# Clock.net
KiCad netlist of a schematic drawn in Altium Designer
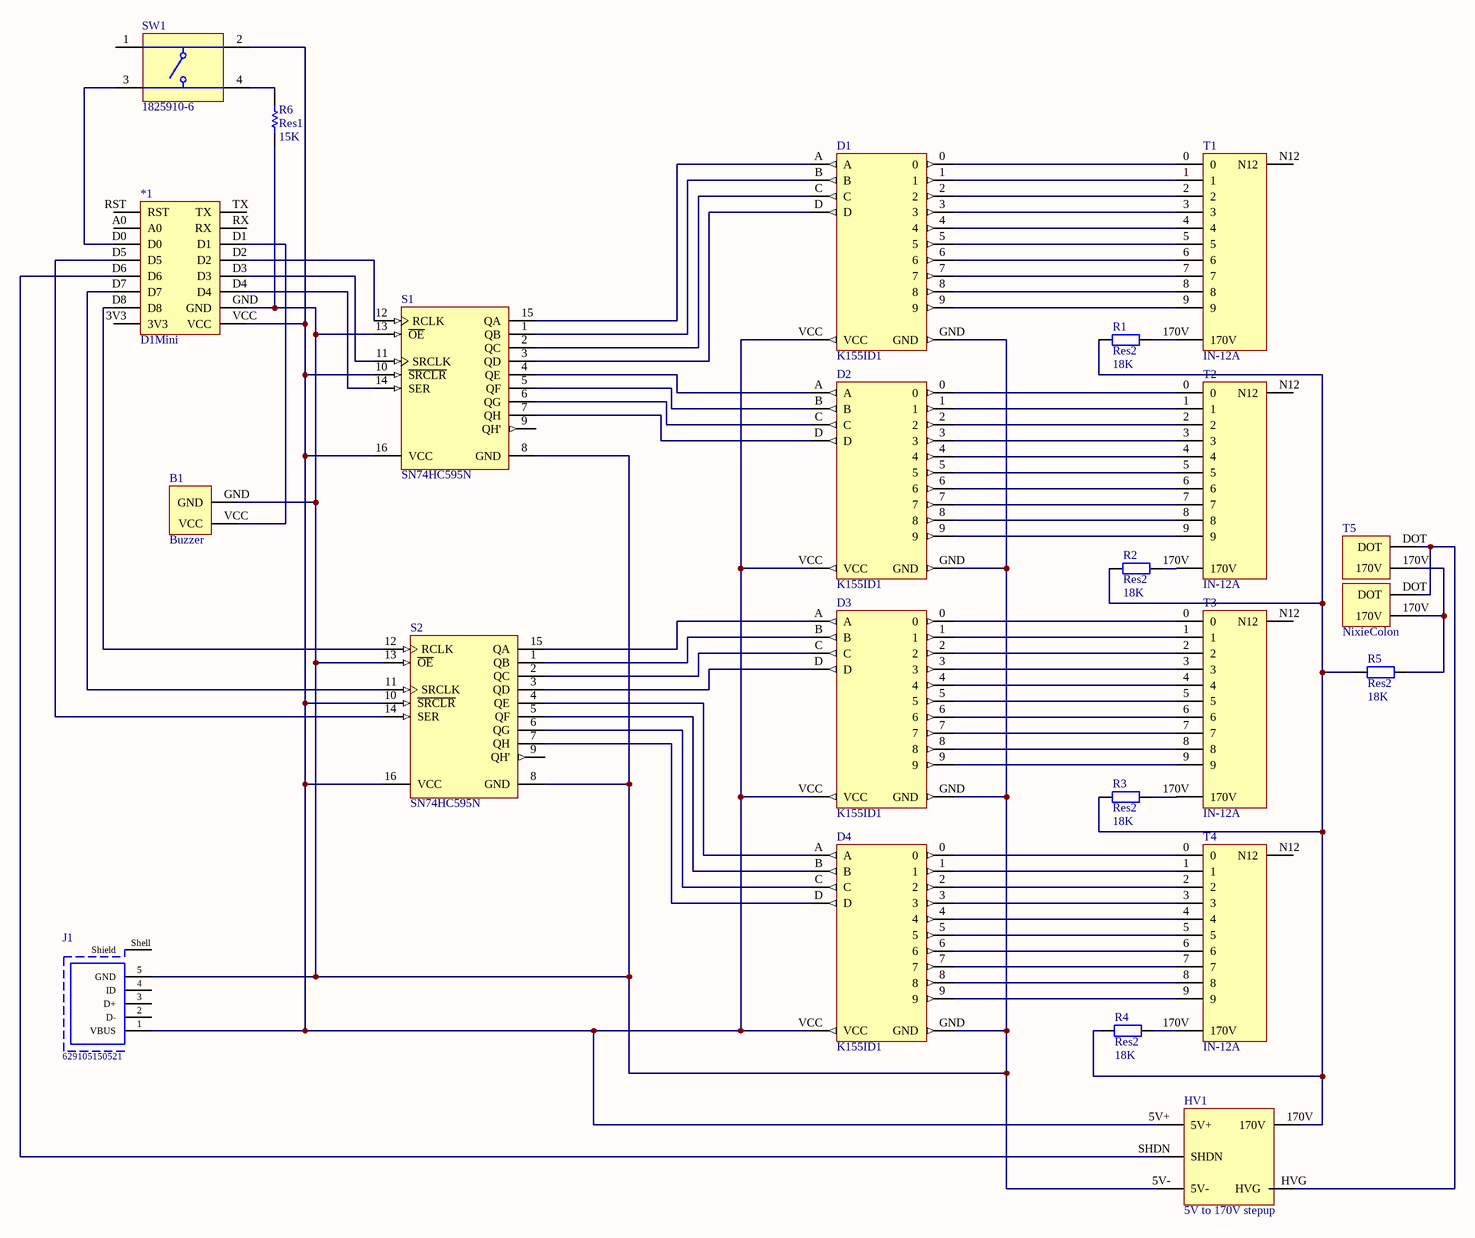
[diagram p0: Clock.SchDoc]

(export (version "E")
  (design (tool "Eeschema 10.0.6"))
  (components
    (comp (ref "*1")
      (value "D1Mini")
      (footprint "DIP16-WemosD1Mini")
      (libsource (lib "NixieTubeClock") (part "D1Mini"))
    )
    (comp (ref "B1") (value "Buzzer") (footprint "Buzzer") (libsource (lib "NixieTubeClock") (part "Buzzer")))
    (comp (ref "D1")
      (value "K155ID1")
      (footprint "DIP16")
      (libsource (lib "NixieTubeClock") (part "K155ID1"))
    )
    (comp (ref "D2")
      (value "K155ID1")
      (footprint "DIP16")
      (libsource (lib "NixieTubeClock") (part "K155ID1"))
    )
    (comp (ref "D3")
      (value "K155ID1")
      (footprint "DIP16")
      (libsource (lib "NixieTubeClock") (part "K155ID1"))
    )
    (comp (ref "D4")
      (value "K155ID1")
      (footprint "DIP16")
      (libsource (lib "NixieTubeClock") (part "K155ID1"))
    )
    (comp (ref "HV1")
      (value "5V to 170V stepup")
      (footprint "5V to 170V stepup")
      (libsource (lib "NixieTubeClock") (part "5V to 170V stepup"))
    )
    (comp (ref "J1")
      (value "629105150521")
      (footprint "629105150521")
      (description "Micro USB 2.0 Type B Receptacle WR-COM, Horizontal, SMT, with Pegs, High Current at Pin 1 & Pin 5")
      (fields (field (name "MANUFACTURER") "Wurth Elektronik") (field (name "PUBLISHER") "WurthElektronik"))
      (libsource (lib "Altium Content Vault") (part "WE-USB-5-1SHLD"))
    )
    (comp (ref "R1")
      (value "Res2")
      (footprint "AXIAL-0.6")
      (description "Resistor")
      (fields (field (name "ALTIUM_VALUE") "18K") (field (name "PUBLISHER") "Altium Limited"))
      (libsource (lib "Miscellaneous Devices") (part "Res2"))
    )
    (comp (ref "R2")
      (value "Res2")
      (footprint "AXIAL-0.6")
      (description "Resistor")
      (fields (field (name "ALTIUM_VALUE") "18K") (field (name "PUBLISHER") "Altium Limited"))
      (libsource (lib "Miscellaneous Devices") (part "Res2"))
    )
    (comp (ref "R3")
      (value "Res2")
      (footprint "AXIAL-0.6")
      (description "Resistor")
      (fields (field (name "ALTIUM_VALUE") "18K") (field (name "PUBLISHER") "Altium Limited"))
      (libsource (lib "Miscellaneous Devices") (part "Res2"))
    )
    (comp (ref "R4")
      (value "Res2")
      (footprint "AXIAL-0.6")
      (description "Resistor")
      (fields (field (name "ALTIUM_VALUE") "18K") (field (name "PUBLISHER") "Altium Limited"))
      (libsource (lib "Miscellaneous Devices") (part "Res2"))
    )
    (comp (ref "R5")
      (value "Res2")
      (footprint "AXIAL-0.6")
      (description "Resistor")
      (fields (field (name "ALTIUM_VALUE") "18K") (field (name "PUBLISHER") "Altium Limited"))
      (libsource (lib "Miscellaneous Devices") (part "Res2"))
    )
    (comp (ref "R6")
      (value "Res1")
      (footprint "AXIAL-0.3")
      (description "Resistor")
      (fields (field (name "ALTIUM_VALUE") "15K") (field (name "PUBLISHER") "Altium Limited"))
      (libsource (lib "Miscellaneous Devices") (part "Res1"))
    )
    (comp (ref "S1")
      (value "SN74HC595N")
      (footprint "N0016A")
      (description "8-Bit Shift Registers With 3-State Output Registers, N0016A, TUBE")
      (fields
        (field (name "GENERIC PART NUMBER") "SN74HC595")
        (field (name "MANUFACTURER") "Texas Instruments")
      )
      (libsource (lib "Altium Content Vault") (part "TI-SN74XHCT595X_SN74LV595A-16"))
    )
    (comp (ref "S2")
      (value "SN74HC595N")
      (footprint "N0016A")
      (description "8-Bit Shift Registers With 3-State Output Registers, N0016A, TUBE")
      (fields
        (field (name "GENERIC PART NUMBER") "SN74HC595")
        (field (name "MANUFACTURER") "Texas Instruments")
      )
      (libsource (lib "Altium Content Vault") (part "TI-SN74XHCT595X_SN74LV595A-16"))
    )
    (comp (ref "SW1")
      (value "1825910-6")
      (footprint "TECO-1825910-6_V")
      (description "Tact Switch, SPST-NO, 0.05 A, -35 to 85 degC, 4-Pin THD, RoHS, Bulk")
      (fields (field (name "MANUFACTURER") "TE Connectivity"))
      (libsource (lib "Altium Content Vault") (part "SW-SPST-4_A"))
    )
    (comp (ref "T1") (value "IN-12A") (footprint "IN-12A") (libsource (lib "NixieTubeClock") (part "IN-12A")))
    (comp (ref "T2") (value "IN-12A") (footprint "IN-12A") (libsource (lib "NixieTubeClock") (part "IN-12A")))
    (comp (ref "T3") (value "IN-12A") (footprint "IN-12A") (libsource (lib "NixieTubeClock") (part "IN-12A")))
    (comp (ref "T4") (value "IN-12A") (footprint "IN-12A") (libsource (lib "NixieTubeClock") (part "IN-12A")))
    (comp (ref "T5")
      (value "NixieColon")
      (footprint "COLON IN-12A")
      (libsource (lib "NixieTubeClock") (part "NixieColon"))
    )
  )
  (nets
    (net (code "1") (name "Net-(*1-PadD0)") (class "Default")
      (node (ref "*1") (pin "D0") (pinfunction "D0_D0") (pintype "passive"))
      (node (ref "SW1") (pin "3") (pinfunction "3_3") (pintype "passive"))
    )
    (net (code "2") (name "Net-(*1-PadD1)") (class "Default")
      (node (ref "*1") (pin "D1") (pinfunction "D1_D1") (pintype "passive"))
      (node (ref "B1") (pin "VCC") (pinfunction "VCC_VCC") (pintype "passive"))
    )
    (net (code "3") (name "Net-(*1-PadD6)") (class "Default")
      (node (ref "*1") (pin "D6") (pinfunction "D6_D6") (pintype "passive"))
      (node (ref "HV1") (pin "SHDN") (pinfunction "SHDN_SHDN") (pintype "passive"))
    )
    (net (code "4") (name "Net-(D1-Pad0)") (class "Default")
      (node (ref "D1") (pin "0") (pinfunction "0_0") (pintype "output"))
      (node (ref "T1") (pin "0") (pinfunction "0_0") (pintype "passive"))
    )
    (net (code "5") (name "Net-(D1-Pad1)") (class "Default")
      (node (ref "D1") (pin "1") (pinfunction "1_1") (pintype "output"))
      (node (ref "T1") (pin "1") (pinfunction "1_1") (pintype "passive"))
    )
    (net (code "6") (name "Net-(D1-Pad2)") (class "Default")
      (node (ref "D1") (pin "2") (pinfunction "2_2") (pintype "output"))
      (node (ref "T1") (pin "2") (pinfunction "2_2") (pintype "passive"))
    )
    (net (code "7") (name "Net-(D1-Pad3)") (class "Default")
      (node (ref "D1") (pin "3") (pinfunction "3_3") (pintype "output"))
      (node (ref "T1") (pin "3") (pinfunction "3_3") (pintype "passive"))
    )
    (net (code "8") (name "Net-(D1-Pad4)") (class "Default")
      (node (ref "D1") (pin "4") (pinfunction "4_4") (pintype "output"))
      (node (ref "T1") (pin "4") (pinfunction "4_4") (pintype "passive"))
    )
    (net (code "9") (name "Net-(D1-Pad5)") (class "Default")
      (node (ref "D1") (pin "5") (pinfunction "5_5") (pintype "output"))
      (node (ref "T1") (pin "5") (pinfunction "5_5") (pintype "passive"))
    )
    (net (code "10") (name "Net-(D1-Pad6)") (class "Default")
      (node (ref "D1") (pin "6") (pinfunction "6_6") (pintype "output"))
      (node (ref "T1") (pin "6") (pinfunction "6_6") (pintype "passive"))
    )
    (net (code "11") (name "Net-(D1-Pad7)") (class "Default")
      (node (ref "D1") (pin "7") (pinfunction "7_7") (pintype "output"))
      (node (ref "T1") (pin "7") (pinfunction "7_7") (pintype "passive"))
    )
    (net (code "12") (name "Net-(D1-Pad8)") (class "Default")
      (node (ref "D1") (pin "8") (pinfunction "8_8") (pintype "output"))
      (node (ref "T1") (pin "8") (pinfunction "8_8") (pintype "passive"))
    )
    (net (code "13") (name "Net-(D1-Pad9)") (class "Default")
      (node (ref "D1") (pin "9") (pinfunction "9_9") (pintype "output"))
      (node (ref "T1") (pin "9") (pinfunction "9_9") (pintype "passive"))
    )
    (net (code "14") (name "Net-(D2-Pad0)") (class "Default")
      (node (ref "D2") (pin "0") (pinfunction "0_0") (pintype "output"))
      (node (ref "T2") (pin "0") (pinfunction "0_0") (pintype "passive"))
    )
    (net (code "15") (name "Net-(D2-Pad1)") (class "Default")
      (node (ref "D2") (pin "1") (pinfunction "1_1") (pintype "output"))
      (node (ref "T2") (pin "1") (pinfunction "1_1") (pintype "passive"))
    )
    (net (code "16") (name "Net-(D2-Pad2)") (class "Default")
      (node (ref "D2") (pin "2") (pinfunction "2_2") (pintype "output"))
      (node (ref "T2") (pin "2") (pinfunction "2_2") (pintype "passive"))
    )
    (net (code "17") (name "Net-(D2-Pad3)") (class "Default")
      (node (ref "D2") (pin "3") (pinfunction "3_3") (pintype "output"))
      (node (ref "T2") (pin "3") (pinfunction "3_3") (pintype "passive"))
    )
    (net (code "18") (name "Net-(D2-Pad4)") (class "Default")
      (node (ref "D2") (pin "4") (pinfunction "4_4") (pintype "output"))
      (node (ref "T2") (pin "4") (pinfunction "4_4") (pintype "passive"))
    )
    (net (code "19") (name "Net-(D2-Pad5)") (class "Default")
      (node (ref "D2") (pin "5") (pinfunction "5_5") (pintype "output"))
      (node (ref "T2") (pin "5") (pinfunction "5_5") (pintype "passive"))
    )
    (net (code "20") (name "Net-(D2-Pad6)") (class "Default")
      (node (ref "D2") (pin "6") (pinfunction "6_6") (pintype "output"))
      (node (ref "T2") (pin "6") (pinfunction "6_6") (pintype "passive"))
    )
    (net (code "21") (name "Net-(D2-Pad7)") (class "Default")
      (node (ref "D2") (pin "7") (pinfunction "7_7") (pintype "output"))
      (node (ref "T2") (pin "7") (pinfunction "7_7") (pintype "passive"))
    )
    (net (code "22") (name "Net-(D2-Pad8)") (class "Default")
      (node (ref "D2") (pin "8") (pinfunction "8_8") (pintype "output"))
      (node (ref "T2") (pin "8") (pinfunction "8_8") (pintype "passive"))
    )
    (net (code "23") (name "Net-(D2-Pad9)") (class "Default")
      (node (ref "D2") (pin "9") (pinfunction "9_9") (pintype "output"))
      (node (ref "T2") (pin "9") (pinfunction "9_9") (pintype "passive"))
    )
    (net (code "24") (name "Net-(D3-Pad0)") (class "Default")
      (node (ref "D3") (pin "0") (pinfunction "0_0") (pintype "output"))
      (node (ref "T3") (pin "0") (pinfunction "0_0") (pintype "passive"))
    )
    (net (code "25") (name "Net-(D3-Pad1)") (class "Default")
      (node (ref "D3") (pin "1") (pinfunction "1_1") (pintype "output"))
      (node (ref "T3") (pin "1") (pinfunction "1_1") (pintype "passive"))
    )
    (net (code "26") (name "Net-(D3-Pad2)") (class "Default")
      (node (ref "D3") (pin "2") (pinfunction "2_2") (pintype "output"))
      (node (ref "T3") (pin "2") (pinfunction "2_2") (pintype "passive"))
    )
    (net (code "27") (name "Net-(D3-Pad3)") (class "Default")
      (node (ref "D3") (pin "3") (pinfunction "3_3") (pintype "output"))
      (node (ref "T3") (pin "3") (pinfunction "3_3") (pintype "passive"))
    )
    (net (code "28") (name "Net-(D3-Pad4)") (class "Default")
      (node (ref "D3") (pin "4") (pinfunction "4_4") (pintype "output"))
      (node (ref "T3") (pin "4") (pinfunction "4_4") (pintype "passive"))
    )
    (net (code "29") (name "Net-(D3-Pad5)") (class "Default")
      (node (ref "D3") (pin "5") (pinfunction "5_5") (pintype "output"))
      (node (ref "T3") (pin "5") (pinfunction "5_5") (pintype "passive"))
    )
    (net (code "30") (name "Net-(D3-Pad6)") (class "Default")
      (node (ref "D3") (pin "6") (pinfunction "6_6") (pintype "output"))
      (node (ref "T3") (pin "6") (pinfunction "6_6") (pintype "passive"))
    )
    (net (code "31") (name "Net-(D3-Pad7)") (class "Default")
      (node (ref "D3") (pin "7") (pinfunction "7_7") (pintype "output"))
      (node (ref "T3") (pin "7") (pinfunction "7_7") (pintype "passive"))
    )
    (net (code "32") (name "Net-(D3-Pad8)") (class "Default")
      (node (ref "D3") (pin "8") (pinfunction "8_8") (pintype "output"))
      (node (ref "T3") (pin "8") (pinfunction "8_8") (pintype "passive"))
    )
    (net (code "33") (name "Net-(D3-Pad9)") (class "Default")
      (node (ref "D3") (pin "9") (pinfunction "9_9") (pintype "output"))
      (node (ref "T3") (pin "9") (pinfunction "9_9") (pintype "passive"))
    )
    (net (code "34") (name "Net-(D4-Pad0)") (class "Default")
      (node (ref "D4") (pin "0") (pinfunction "0_0") (pintype "output"))
      (node (ref "T4") (pin "0") (pinfunction "0_0") (pintype "passive"))
    )
    (net (code "35") (name "Net-(D4-Pad1)") (class "Default")
      (node (ref "D4") (pin "1") (pinfunction "1_1") (pintype "output"))
      (node (ref "T4") (pin "1") (pinfunction "1_1") (pintype "passive"))
    )
    (net (code "36") (name "Net-(D4-Pad2)") (class "Default")
      (node (ref "D4") (pin "2") (pinfunction "2_2") (pintype "output"))
      (node (ref "T4") (pin "2") (pinfunction "2_2") (pintype "passive"))
    )
    (net (code "37") (name "Net-(D4-Pad3)") (class "Default")
      (node (ref "D4") (pin "3") (pinfunction "3_3") (pintype "output"))
      (node (ref "T4") (pin "3") (pinfunction "3_3") (pintype "passive"))
    )
    (net (code "38") (name "Net-(D4-Pad4)") (class "Default")
      (node (ref "D4") (pin "4") (pinfunction "4_4") (pintype "output"))
      (node (ref "T4") (pin "4") (pinfunction "4_4") (pintype "passive"))
    )
    (net (code "39") (name "Net-(D4-Pad5)") (class "Default")
      (node (ref "D4") (pin "5") (pinfunction "5_5") (pintype "output"))
      (node (ref "T4") (pin "5") (pinfunction "5_5") (pintype "passive"))
    )
    (net (code "40") (name "Net-(D4-Pad6)") (class "Default")
      (node (ref "D4") (pin "6") (pinfunction "6_6") (pintype "output"))
      (node (ref "T4") (pin "6") (pinfunction "6_6") (pintype "passive"))
    )
    (net (code "41") (name "Net-(D4-Pad7)") (class "Default")
      (node (ref "D4") (pin "7") (pinfunction "7_7") (pintype "output"))
      (node (ref "T4") (pin "7") (pinfunction "7_7") (pintype "passive"))
    )
    (net (code "42") (name "Net-(D4-Pad8)") (class "Default")
      (node (ref "D4") (pin "8") (pinfunction "8_8") (pintype "output"))
      (node (ref "T4") (pin "8") (pinfunction "8_8") (pintype "passive"))
    )
    (net (code "43") (name "Net-(D4-Pad9)") (class "Default")
      (node (ref "D4") (pin "9") (pinfunction "9_9") (pintype "output"))
      (node (ref "T4") (pin "9") (pinfunction "9_9") (pintype "passive"))
    )
    (net (code "44") (name "Net-(HV1-Pad170V)") (class "Default")
      (node (ref "HV1") (pin "170V") (pinfunction "170V_170V") (pintype "passive"))
      (node (ref "R1") (pin "2") (pinfunction "2_2") (pintype "passive"))
      (node (ref "R2") (pin "2") (pinfunction "2_2") (pintype "passive"))
      (node (ref "R3") (pin "2") (pinfunction "2_2") (pintype "passive"))
      (node (ref "R4") (pin "2") (pinfunction "2_2") (pintype "passive"))
      (node (ref "R5") (pin "2") (pinfunction "2_2") (pintype "passive"))
    )
    (net (code "45") (name "Net-(HV1-PadHVG)") (class "Default")
      (node (ref "HV1") (pin "HVG") (pinfunction "HVG_HVG") (pintype "passive"))
      (node (ref "T5") (pin "DOT") (pinfunction "DOT_DOT") (pintype "passive"))
    )
    (net (code "46") (name "Net-(J1-GND)") (class "Default")
      (node (ref "*1") (pin "GND") (pinfunction "GND_GND") (pintype "passive"))
      (node (ref "B1") (pin "GND") (pinfunction "GND_GND") (pintype "passive"))
      (node (ref "D1") (pin "GND") (pinfunction "GND_GND") (pintype "output"))
      (node (ref "D2") (pin "GND") (pinfunction "GND_GND") (pintype "output"))
      (node (ref "D3") (pin "GND") (pinfunction "GND_GND") (pintype "output"))
      (node (ref "D4") (pin "GND") (pinfunction "GND_GND") (pintype "output"))
      (node (ref "HV1") (pin "5V-") (pinfunction "5V-_5V-") (pintype "passive"))
      (node (ref "J1") (pin "5") (pinfunction "GND_5") (pintype "passive"))
      (node (ref "R6") (pin "1") (pinfunction "1_1") (pintype "passive"))
      (node (ref "S1") (pin "13") (pinfunction "~{OE}_13") (pintype "input"))
      (node (ref "S1") (pin "8") (pinfunction "GND_8") (pintype "power_in"))
      (node (ref "S2") (pin "13") (pinfunction "~{OE}_13") (pintype "input"))
      (node (ref "S2") (pin "8") (pinfunction "GND_8") (pintype "power_in"))
    )
    (net (code "47") (name "Net-(J1-VBUS)") (class "Default")
      (node (ref "*1") (pin "VCC") (pinfunction "VCC_VCC") (pintype "passive"))
      (node (ref "D1") (pin "VCC") (pinfunction "VCC_VCC") (pintype "output"))
      (node (ref "D2") (pin "VCC") (pinfunction "VCC_VCC") (pintype "output"))
      (node (ref "D3") (pin "VCC") (pinfunction "VCC_VCC") (pintype "output"))
      (node (ref "D4") (pin "VCC") (pinfunction "VCC_VCC") (pintype "output"))
      (node (ref "HV1") (pin "5V+") (pinfunction "5V+_5V+") (pintype "passive"))
      (node (ref "J1") (pin "1") (pinfunction "VBUS_1") (pintype "passive"))
      (node (ref "S1") (pin "10") (pinfunction "~{SRCLR}_10") (pintype "input"))
      (node (ref "S1") (pin "16") (pinfunction "VCC_16") (pintype "power_in"))
      (node (ref "S2") (pin "10") (pinfunction "~{SRCLR}_10") (pintype "input"))
      (node (ref "S2") (pin "16") (pinfunction "VCC_16") (pintype "power_in"))
      (node (ref "SW1") (pin "2") (pinfunction "2_2") (pintype "passive"))
    )
    (net (code "48") (name "Net-(R1-Pad1)") (class "Default")
      (node (ref "R1") (pin "1") (pinfunction "1_1") (pintype "passive"))
      (node (ref "T1") (pin "170V") (pinfunction "170V_170V") (pintype "passive"))
    )
    (net (code "49") (name "Net-(R2-Pad1)") (class "Default")
      (node (ref "R2") (pin "1") (pinfunction "1_1") (pintype "passive"))
      (node (ref "T2") (pin "170V") (pinfunction "170V_170V") (pintype "passive"))
    )
    (net (code "50") (name "Net-(R3-Pad1)") (class "Default")
      (node (ref "R3") (pin "1") (pinfunction "1_1") (pintype "passive"))
      (node (ref "T3") (pin "170V") (pinfunction "170V_170V") (pintype "passive"))
    )
    (net (code "51") (name "Net-(R4-Pad1)") (class "Default")
      (node (ref "R4") (pin "1") (pinfunction "1_1") (pintype "passive"))
      (node (ref "T4") (pin "170V") (pinfunction "170V_170V") (pintype "passive"))
    )
    (net (code "52") (name "Net-(R5-Pad1)") (class "Default")
      (node (ref "R5") (pin "1") (pinfunction "1_1") (pintype "passive"))
      (node (ref "T5") (pin "170V") (pinfunction "170V_170V") (pintype "passive"))
    )
    (net (code "53") (name "Net-(R6-Pad2)") (class "Default")
      (node (ref "R6") (pin "2") (pinfunction "2_2") (pintype "passive"))
      (node (ref "SW1") (pin "4") (pinfunction "4_4") (pintype "passive"))
    )
    (net (code "54") (name "Net-(S1-QA)") (class "Default")
      (node (ref "D1") (pin "A") (pinfunction "A_A") (pintype "output"))
      (node (ref "S1") (pin "15") (pinfunction "QA_15") (pintype "tri_state"))
    )
    (net (code "55") (name "Net-(S1-QB)") (class "Default")
      (node (ref "D1") (pin "B") (pinfunction "B_B") (pintype "output"))
      (node (ref "S1") (pin "1") (pinfunction "QB_1") (pintype "tri_state"))
    )
    (net (code "56") (name "Net-(S1-QC)") (class "Default")
      (node (ref "D1") (pin "C") (pinfunction "C_C") (pintype "output"))
      (node (ref "S1") (pin "2") (pinfunction "QC_2") (pintype "tri_state"))
    )
    (net (code "57") (name "Net-(S1-QD)") (class "Default")
      (node (ref "D1") (pin "D") (pinfunction "D_D") (pintype "output"))
      (node (ref "S1") (pin "3") (pinfunction "QD_3") (pintype "tri_state"))
    )
    (net (code "58") (name "Net-(S1-QE)") (class "Default")
      (node (ref "D2") (pin "A") (pinfunction "A_A") (pintype "output"))
      (node (ref "S1") (pin "4") (pinfunction "QE_4") (pintype "tri_state"))
    )
    (net (code "59") (name "Net-(S1-QF)") (class "Default")
      (node (ref "D2") (pin "B") (pinfunction "B_B") (pintype "output"))
      (node (ref "S1") (pin "5") (pinfunction "QF_5") (pintype "tri_state"))
    )
    (net (code "60") (name "Net-(S1-QG)") (class "Default")
      (node (ref "D2") (pin "C") (pinfunction "C_C") (pintype "output"))
      (node (ref "S1") (pin "6") (pinfunction "QG_6") (pintype "tri_state"))
    )
    (net (code "61") (name "Net-(S1-QH)") (class "Default")
      (node (ref "D2") (pin "D") (pinfunction "D_D") (pintype "output"))
      (node (ref "S1") (pin "7") (pinfunction "QH_7") (pintype "tri_state"))
    )
    (net (code "62") (name "Net-(S1-RCLK)") (class "Default")
      (node (ref "*1") (pin "D2") (pinfunction "D2_D2") (pintype "passive"))
      (node (ref "S1") (pin "12") (pinfunction "RCLK_12") (pintype "input"))
    )
    (net (code "63") (name "Net-(S1-SER)") (class "Default")
      (node (ref "*1") (pin "D4") (pinfunction "D4_D4") (pintype "passive"))
      (node (ref "S1") (pin "14") (pinfunction "SER_14") (pintype "input"))
    )
    (net (code "64") (name "Net-(S1-SRCLK)") (class "Default")
      (node (ref "*1") (pin "D3") (pinfunction "D3_D3") (pintype "passive"))
      (node (ref "S1") (pin "11") (pinfunction "SRCLK_11") (pintype "input"))
    )
    (net (code "65") (name "Net-(S2-QA)") (class "Default")
      (node (ref "D3") (pin "A") (pinfunction "A_A") (pintype "output"))
      (node (ref "S2") (pin "15") (pinfunction "QA_15") (pintype "tri_state"))
    )
    (net (code "66") (name "Net-(S2-QB)") (class "Default")
      (node (ref "D3") (pin "B") (pinfunction "B_B") (pintype "output"))
      (node (ref "S2") (pin "1") (pinfunction "QB_1") (pintype "tri_state"))
    )
    (net (code "67") (name "Net-(S2-QC)") (class "Default")
      (node (ref "D3") (pin "C") (pinfunction "C_C") (pintype "output"))
      (node (ref "S2") (pin "2") (pinfunction "QC_2") (pintype "tri_state"))
    )
    (net (code "68") (name "Net-(S2-QD)") (class "Default")
      (node (ref "D3") (pin "D") (pinfunction "D_D") (pintype "output"))
      (node (ref "S2") (pin "3") (pinfunction "QD_3") (pintype "tri_state"))
    )
    (net (code "69") (name "Net-(S2-QE)") (class "Default")
      (node (ref "D4") (pin "A") (pinfunction "A_A") (pintype "output"))
      (node (ref "S2") (pin "4") (pinfunction "QE_4") (pintype "tri_state"))
    )
    (net (code "70") (name "Net-(S2-QF)") (class "Default")
      (node (ref "D4") (pin "B") (pinfunction "B_B") (pintype "output"))
      (node (ref "S2") (pin "5") (pinfunction "QF_5") (pintype "tri_state"))
    )
    (net (code "71") (name "Net-(S2-QG)") (class "Default")
      (node (ref "D4") (pin "C") (pinfunction "C_C") (pintype "output"))
      (node (ref "S2") (pin "6") (pinfunction "QG_6") (pintype "tri_state"))
    )
    (net (code "72") (name "Net-(S2-QH)") (class "Default")
      (node (ref "D4") (pin "D") (pinfunction "D_D") (pintype "output"))
      (node (ref "S2") (pin "7") (pinfunction "QH_7") (pintype "tri_state"))
    )
    (net (code "73") (name "Net-(S2-RCLK)") (class "Default")
      (node (ref "*1") (pin "D8") (pinfunction "D8_D8") (pintype "passive"))
      (node (ref "S2") (pin "12") (pinfunction "RCLK_12") (pintype "input"))
    )
    (net (code "74") (name "Net-(S2-SER)") (class "Default")
      (node (ref "*1") (pin "D5") (pinfunction "D5_D5") (pintype "passive"))
      (node (ref "S2") (pin "14") (pinfunction "SER_14") (pintype "input"))
    )
    (net (code "75") (name "Net-(S2-SRCLK)") (class "Default")
      (node (ref "*1") (pin "D7") (pinfunction "D7_D7") (pintype "passive"))
      (node (ref "S2") (pin "11") (pinfunction "SRCLK_11") (pintype "input"))
    )
    (net (code "76") (name "unconnected-(*1-Pad3V3)") (class "Default")
      (node (ref "*1") (pin "3V3") (pinfunction "3V3_3V3") (pintype "passive"))
    )
    (net (code "77") (name "unconnected-(*1-PadA0)") (class "Default")
      (node (ref "*1") (pin "A0") (pinfunction "A0_A0") (pintype "passive"))
    )
    (net (code "78") (name "unconnected-(*1-PadRST)") (class "Default")
      (node (ref "*1") (pin "RST") (pinfunction "RST_RST") (pintype "passive"))
    )
    (net (code "79") (name "unconnected-(*1-PadRX)") (class "Default")
      (node (ref "*1") (pin "RX") (pinfunction "RX_RX") (pintype "passive"))
    )
    (net (code "80") (name "unconnected-(*1-PadTX)") (class "Default")
      (node (ref "*1") (pin "TX") (pinfunction "TX_TX") (pintype "passive"))
    )
    (net (code "81") (name "unconnected-(J1-D+-Pad3)") (class "Default")
      (node (ref "J1") (pin "3") (pinfunction "D+_3") (pintype "passive"))
    )
    (net (code "82") (name "unconnected-(J1-D--Pad2)") (class "Default")
      (node (ref "J1") (pin "2") (pinfunction "D-_2") (pintype "passive"))
    )
    (net (code "83") (name "unconnected-(J1-ID-Pad4)") (class "Default")
      (node (ref "J1") (pin "4") (pinfunction "ID_4") (pintype "passive"))
    )
    (net (code "84") (name "unconnected-(J1-Shield-PadShell)") (class "Default")
      (node (ref "J1") (pin "Shell") (pinfunction "Shield_Shell") (pintype "passive"))
    )
    (net (code "85") (name "unconnected-(S1-QH'-Pad9)") (class "Default")
      (node (ref "S1") (pin "9") (pinfunction "QH'_9") (pintype "output"))
    )
    (net (code "86") (name "unconnected-(S2-QH'-Pad9)") (class "Default")
      (node (ref "S2") (pin "9") (pinfunction "QH'_9") (pintype "output"))
    )
    (net (code "87") (name "unconnected-(SW1-Pad1)") (class "Default")
      (node (ref "SW1") (pin "1") (pinfunction "1_1") (pintype "passive"))
    )
    (net (code "88") (name "unconnected-(T1-PadN12)") (class "Default")
      (node (ref "T1") (pin "N12") (pinfunction "N12_N12") (pintype "passive"))
    )
    (net (code "89") (name "unconnected-(T2-PadN12)") (class "Default")
      (node (ref "T2") (pin "N12") (pinfunction "N12_N12") (pintype "passive"))
    )
    (net (code "90") (name "unconnected-(T3-PadN12)") (class "Default")
      (node (ref "T3") (pin "N12") (pinfunction "N12_N12") (pintype "passive"))
    )
    (net (code "91") (name "unconnected-(T4-PadN12)") (class "Default")
      (node (ref "T4") (pin "N12") (pinfunction "N12_N12") (pintype "passive"))
    )
  )
)
